# 06_LEDs.net
KiCad netlist of a schematic drawn in Altium Designer
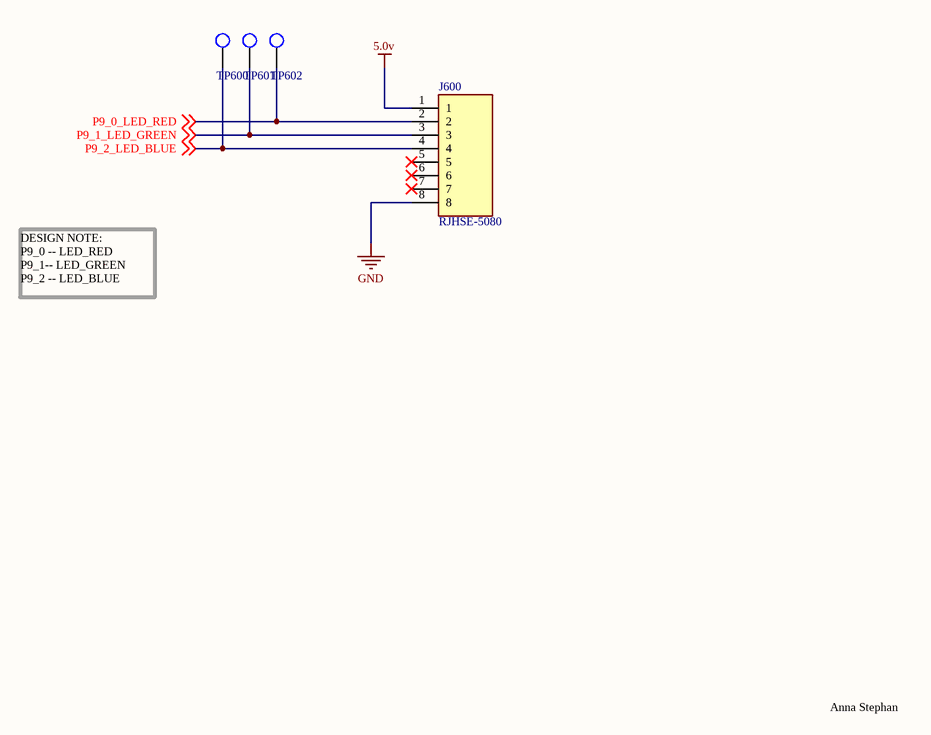
[diagram p0: 06_LEDs.SchDoc]

(export (version "E")
  (design (tool "Eeschema 10.0.6"))
  (components
    (comp (ref "J600")
      (value "RJHSE-5080")
      (footprint "CONN_RJSBE5080_16P13X12P57_AMP")
      (description "Jack Modular Connector 8p8c (RJ45, Ethernet) 90Â° Angle (Right) Unshielded")
      (fields
        (field (name "MF") "Amphenol Commercial Products")
        (field (name "DIGI-KEY_PART_NUMBER") "RJHSE-5080-ND")
      )
      (libsource (lib "453lib") (part "RJHSE-5080"))
    )
    (comp (ref "TP600")
      (value "TP_1206")
      (footprint "TP-SMC-1206")
      (description "Test Point SMD 1206")
      (fields
        (field (name "MANUFACTURER") "TE Connectivity (Tyco Electronics)")
        (field (name "MANUFACTURER PART NUMBER") "1625854-1")
      )
      (libsource (lib "ECE453-S22") (part "TP_1206"))
    )
    (comp (ref "TP601")
      (value "TP_1206")
      (footprint "TP-SMC-1206")
      (description "Test Point SMD 1206")
      (fields
        (field (name "MANUFACTURER") "TE Connectivity (Tyco Electronics)")
        (field (name "MANUFACTURER PART NUMBER") "1625854-1")
      )
      (libsource (lib "ECE453-S22") (part "TP_1206"))
    )
    (comp (ref "TP602")
      (value "TP_1206")
      (footprint "TP-SMC-1206")
      (description "Test Point SMD 1206")
      (fields
        (field (name "MANUFACTURER") "TE Connectivity (Tyco Electronics)")
        (field (name "MANUFACTURER PART NUMBER") "1625854-1")
      )
      (libsource (lib "ECE453-S22") (part "TP_1206"))
    )
  )
  (nets
    (net (code "1") (name "5.0v") (class "Default")
      (node (ref "J600") (pin "1") (pinfunction "1_1") (pintype "passive"))
    )
    (net (code "2") (name "GND") (class "Default")
      (node (ref "J600") (pin "8") (pinfunction "8_8") (pintype "passive"))
    )
    (net (code "3") (name "P9_0_LED_RED") (class "Default")
      (node (ref "J600") (pin "2") (pinfunction "2_2") (pintype "passive"))
      (node (ref "TP602") (pin "1") (pintype "passive"))
    )
    (net (code "4") (name "P9_1_LED_GREEN") (class "Default")
      (node (ref "J600") (pin "3") (pinfunction "3_3") (pintype "passive"))
      (node (ref "TP601") (pin "1") (pintype "passive"))
    )
    (net (code "5") (name "P9_2_LED_BLUE") (class "Default")
      (node (ref "J600") (pin "4") (pinfunction "4_4") (pintype "passive"))
      (node (ref "TP600") (pin "1") (pintype "passive"))
    )
    (net (code "6") (name "unconnected-(J600-Pad5)") (class "Default")
      (node (ref "J600") (pin "5") (pinfunction "5_5") (pintype "passive+no_connect"))
    )
    (net (code "7") (name "unconnected-(J600-Pad6)") (class "Default")
      (node (ref "J600") (pin "6") (pinfunction "6_6") (pintype "passive+no_connect"))
    )
    (net (code "8") (name "unconnected-(J600-Pad7)") (class "Default")
      (node (ref "J600") (pin "7") (pinfunction "7_7") (pintype "passive+no_connect"))
    )
  )
)
